# Board_v1.net
KiCad netlist of a schematic drawn in EAGLE
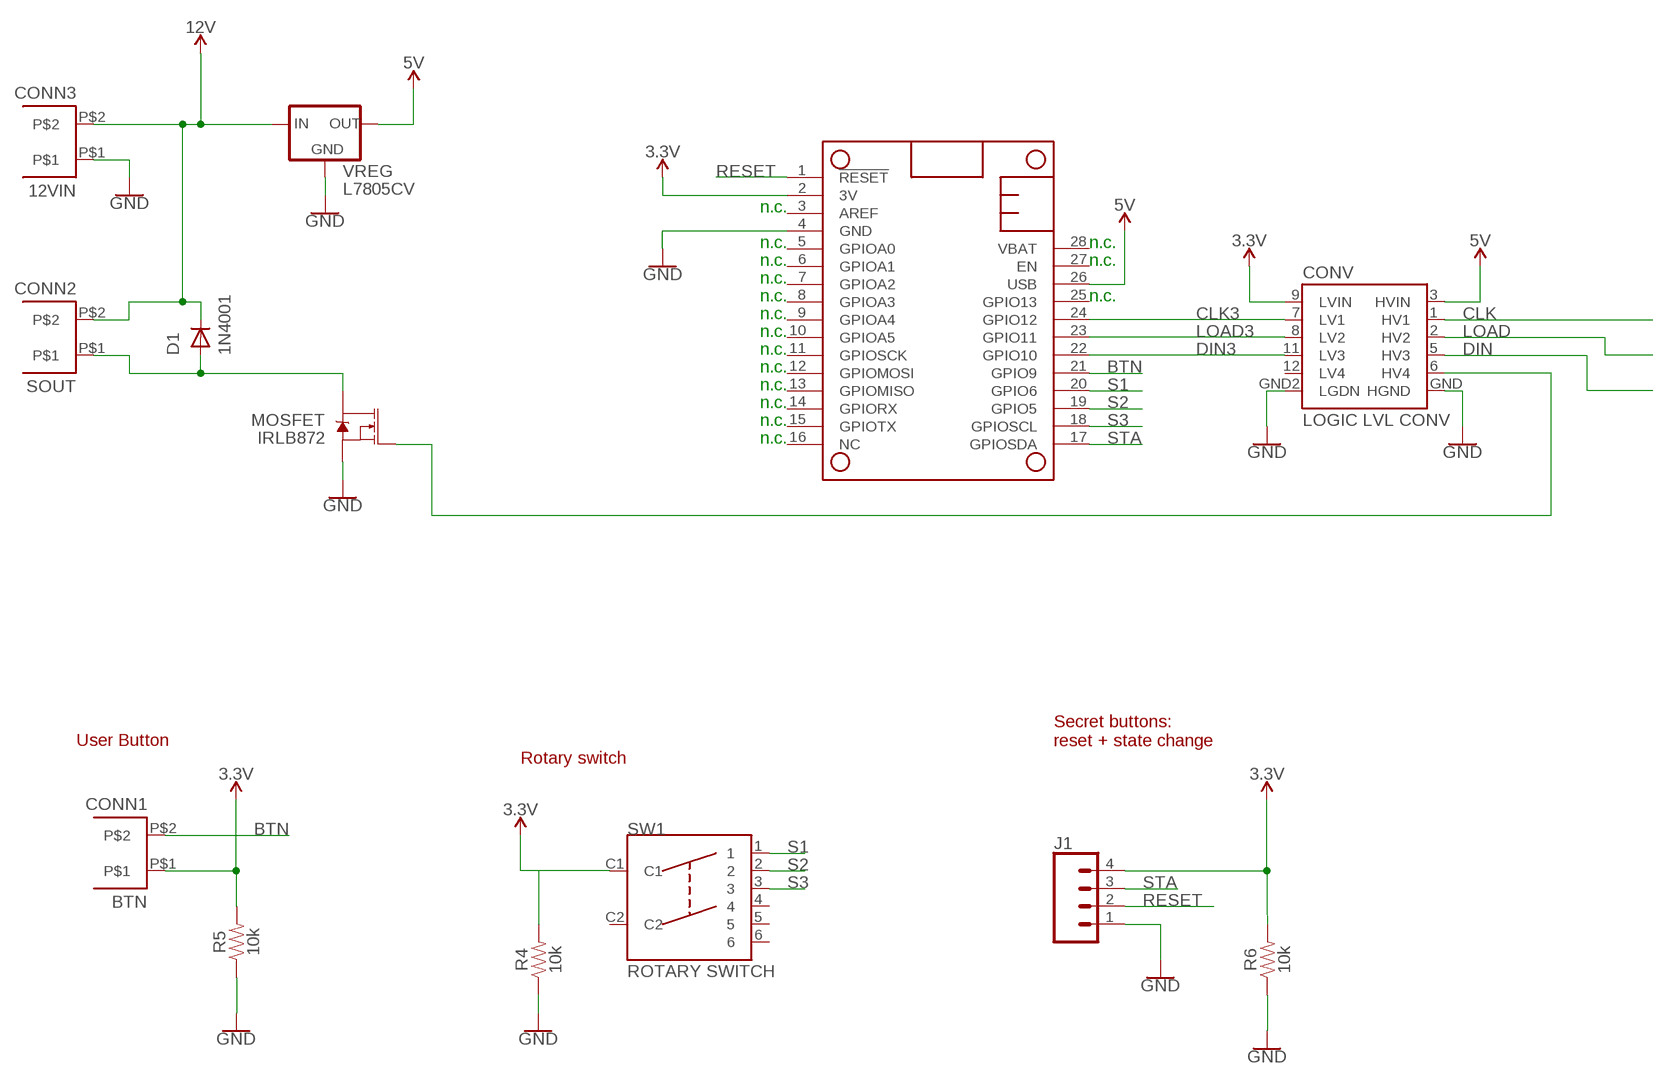
[diagram p0: schematic, sheet 1, part 1 of 3]
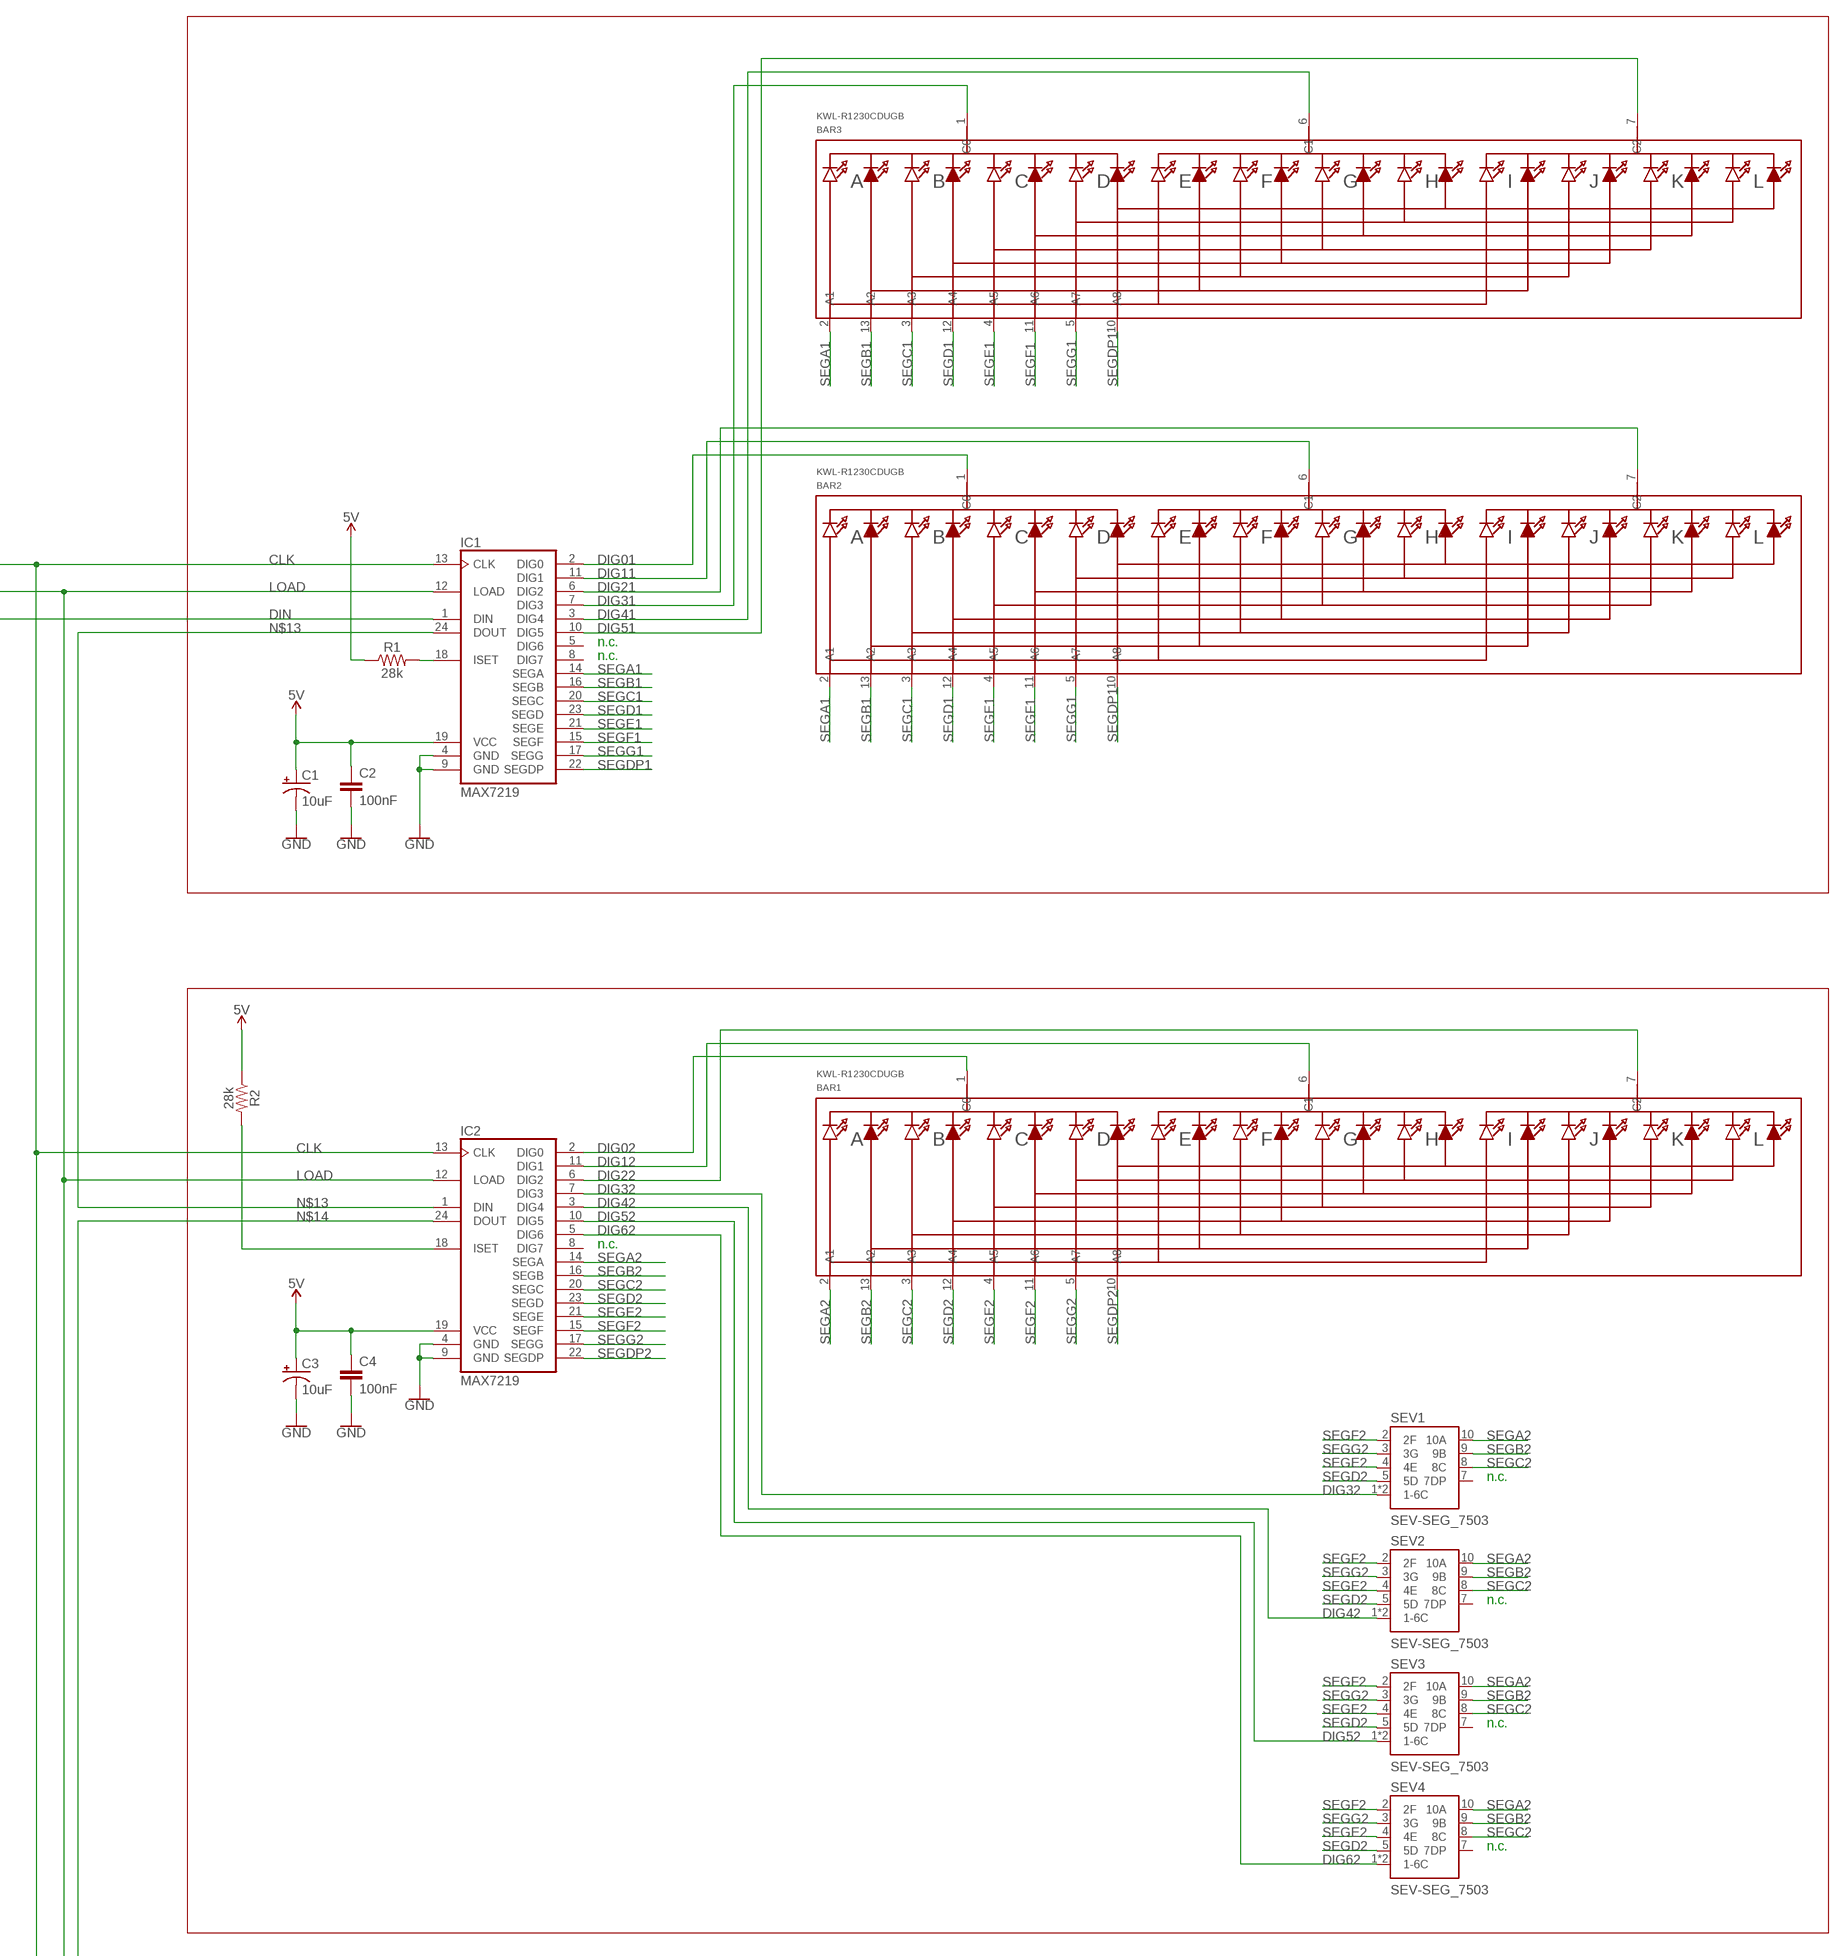
[diagram p1: schematic, sheet 1, part 2 of 3]
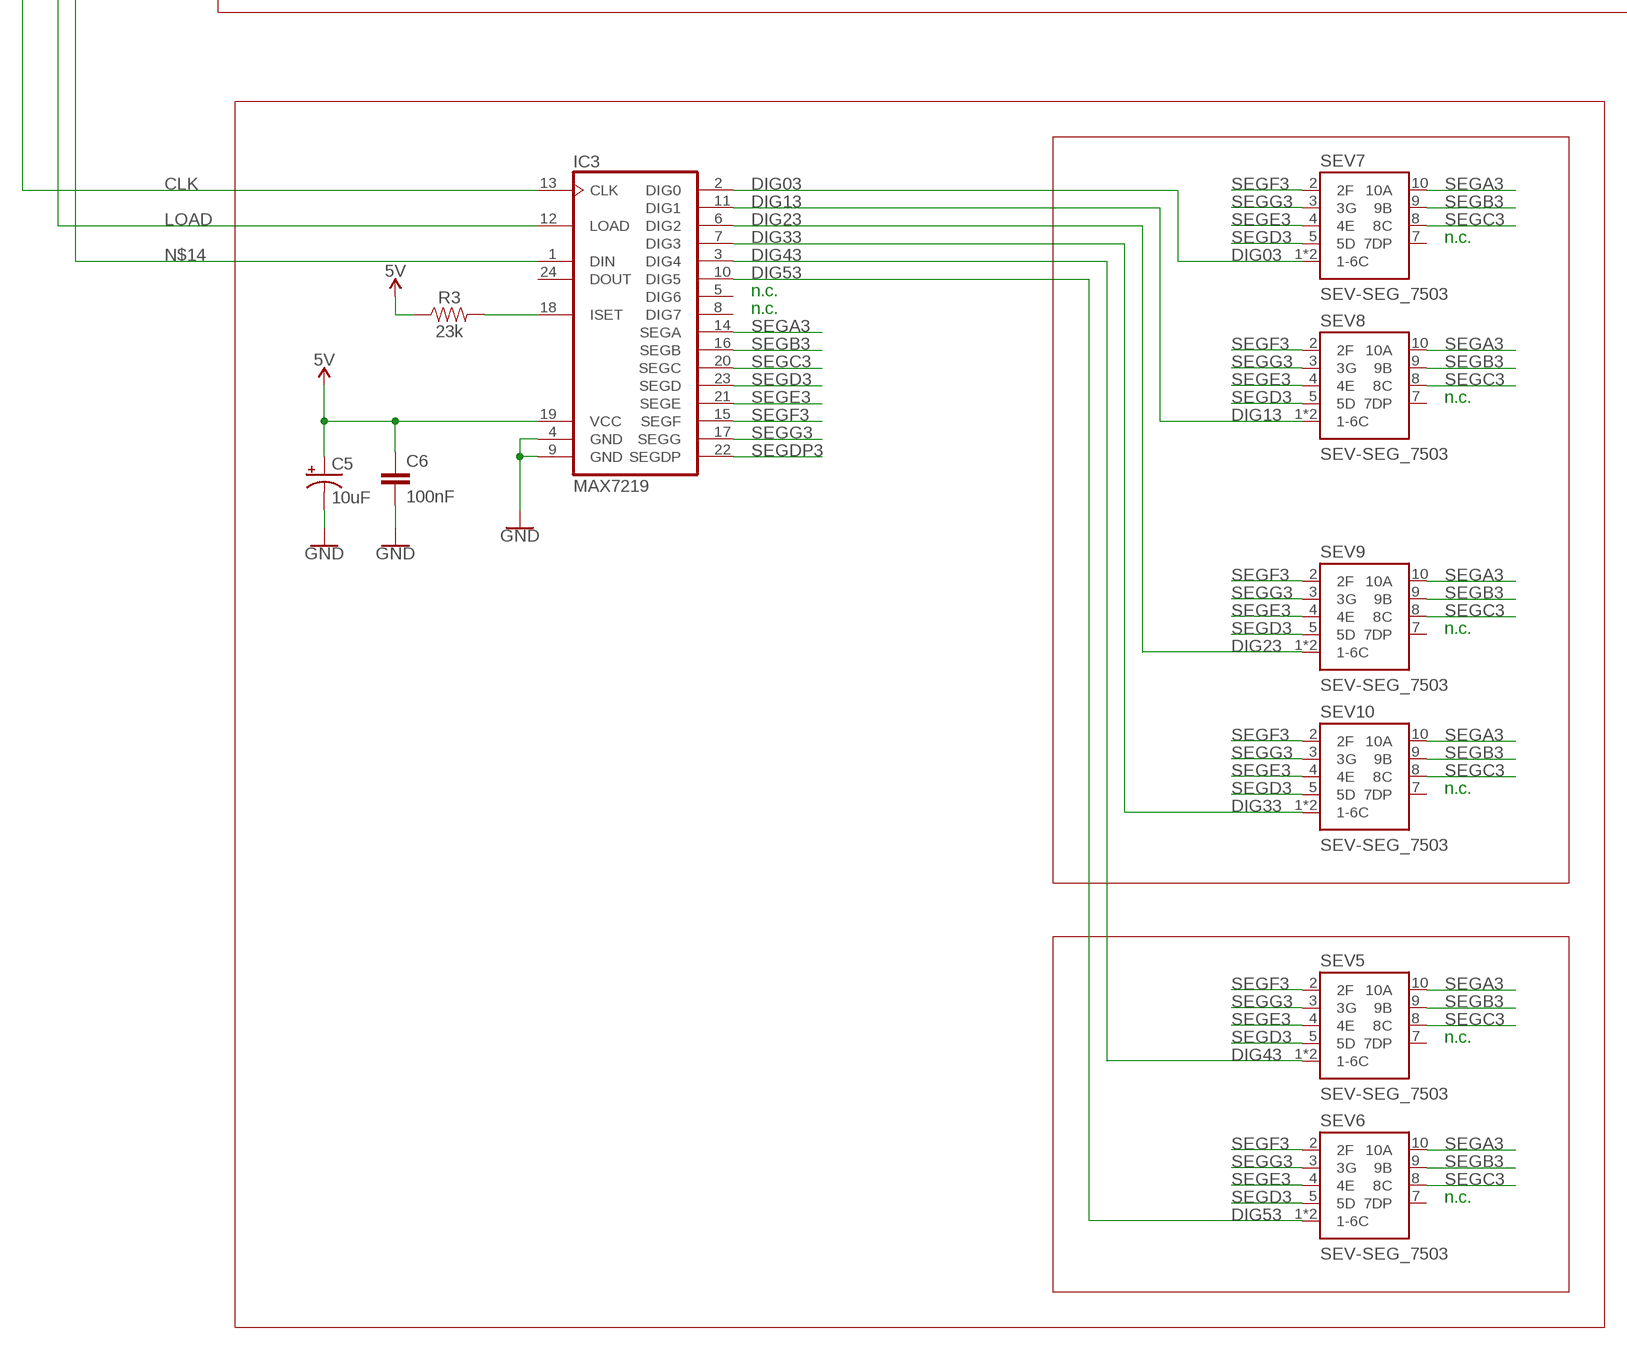
[diagram p2: schematic, sheet 1, part 3 of 3]

(export (version "E")
  (design (tool "Eeschema 10.0.6"))
  (components
    (comp (ref "12VIN")
      (value "CONN3")
      (footprint "eagle-import:MICRO-FIT_43560_3MM")
      (libsource (lib "eagle-import") (part "MICRO-FIT_3.0_43650"))
    )
    (comp (ref "BAR1")
      (value "KWL-R1230CDUGB")
      (footprint "eagle-import:SEGMENT_BICOL_BL-AR12Z3010")
      (libsource (lib "eagle-import") (part "KWL-R1230CDUGB"))
    )
    (comp (ref "BAR2")
      (value "KWL-R1230CDUGB")
      (footprint "eagle-import:SEGMENT_BICOL_BL-AR12Z3010")
      (libsource (lib "eagle-import") (part "KWL-R1230CDUGB"))
    )
    (comp (ref "BAR3")
      (value "KWL-R1230CDUGB")
      (footprint "eagle-import:SEGMENT_BICOL_BL-AR12Z3010")
      (libsource (lib "eagle-import") (part "KWL-R1230CDUGB"))
    )
    (comp (ref "BTN")
      (value "CONN1")
      (footprint "eagle-import:MICRO-FIT_43560_3MM")
      (libsource (lib "eagle-import") (part "MICRO-FIT_3.0_43650"))
    )
    (comp (ref "C1")
      (value "10uF")
      (footprint "eagle-import:CPOL-RADIAL-2.5MM-5MM-KIT")
      (libsource (lib "eagle-import") (part "CAP_POL"))
    )
    (comp (ref "C2")
      (value "100nF")
      (footprint "eagle-import:CAP-PTH-5MM")
      (libsource (lib "eagle-import") (part "CAP_CERAMIC"))
    )
    (comp (ref "C3")
      (value "10uF")
      (footprint "eagle-import:CPOL-RADIAL-2.5MM-5MM-KIT")
      (libsource (lib "eagle-import") (part "CAP_POL"))
    )
    (comp (ref "C4")
      (value "100nF")
      (footprint "eagle-import:CAP-PTH-5MM")
      (libsource (lib "eagle-import") (part "CAP_CERAMIC"))
    )
    (comp (ref "C5")
      (value "10uF")
      (footprint "eagle-import:CPOL-RADIAL-2.5MM-5MM-KIT")
      (libsource (lib "eagle-import") (part "CAP_POL"))
    )
    (comp (ref "C6")
      (value "100nF")
      (footprint "eagle-import:CAP-PTH-5MM")
      (libsource (lib "eagle-import") (part "CAP_CERAMIC"))
    )
    (comp (ref "CONV")
      (value "LOGIC LVL CONV")
      (footprint "eagle-import:3-5V_LOGIC_LVL_CONV")
      (libsource (lib "eagle-import") (part "3-5V_LOGIC_LVL_CONV"))
    )
    (comp (ref "D1")
      (value "1N4001")
      (footprint "eagle-import:CASE59−10-AXIAL")
      (libsource (lib "eagle-import") (part "1N4001"))
    )
    (comp (ref "FEATHERM0")
      (value "FEATHERWING_NODIM")
      (footprint "eagle-import:FEATHER")
      (libsource (lib "eagle-import") (part "FEATHERWING_NODIM"))
    )
    (comp (ref "IC1")
      (value "MAX7219")
      (footprint "eagle-import:DIL24-3")
      (fields (field (name "MF") "MAXIM") (field (name "MPN") "MAX7219CNG"))
      (libsource (lib "eagle-import") (part "MAX7219CNG"))
    )
    (comp (ref "IC2")
      (value "MAX7219")
      (footprint "eagle-import:DIL24-3")
      (fields (field (name "MF") "MAXIM") (field (name "MPN") "MAX7219CNG"))
      (libsource (lib "eagle-import") (part "MAX7219CNG"))
    )
    (comp (ref "IC3")
      (value "MAX7219")
      (footprint "eagle-import:DIL24-3")
      (fields (field (name "MF") "MAXIM") (field (name "MPN") "MAX7219CNG"))
      (libsource (lib "eagle-import") (part "MAX7219CNG"))
    )
    (comp (ref "J1")
      (value "CONN_041X04_NO_SILK")
      (footprint "eagle-import:1X04_NO_SILK")
      (libsource (lib "eagle-import") (part "CONN_041X04_NO_SILK"))
    )
    (comp (ref "MOSFET")
      (value "IRLB872")
      (footprint "eagle-import:TO-220-ALT")
      (libsource (lib "eagle-import") (part "IRLB872"))
    )
    (comp (ref "R1")
      (value "28k")
      (footprint "eagle-import:AXIAL-0.3")
      (libsource (lib "eagle-import") (part "RESISTOR"))
    )
    (comp (ref "R2")
      (value "28k")
      (footprint "eagle-import:AXIAL-0.3")
      (libsource (lib "eagle-import") (part "RESISTOR"))
    )
    (comp (ref "R3")
      (value "23k")
      (footprint "eagle-import:AXIAL-0.3")
      (libsource (lib "eagle-import") (part "RESISTOR"))
    )
    (comp (ref "R4")
      (value "10k")
      (footprint "eagle-import:AXIAL-0.3")
      (libsource (lib "eagle-import") (part "RESISTOR"))
    )
    (comp (ref "R5")
      (value "10k")
      (footprint "eagle-import:AXIAL-0.3")
      (libsource (lib "eagle-import") (part "RESISTOR"))
    )
    (comp (ref "R6")
      (value "10k")
      (footprint "eagle-import:AXIAL-0.3")
      (libsource (lib "eagle-import") (part "RESISTOR"))
    )
    (comp (ref "SEV1")
      (value "SEV-SEG_7503")
      (footprint "eagle-import:HDSP-7503-C")
      (libsource (lib "eagle-import") (part "SEV-SEG_7503"))
    )
    (comp (ref "SEV2")
      (value "SEV-SEG_7503")
      (footprint "eagle-import:HDSP-7503-C")
      (libsource (lib "eagle-import") (part "SEV-SEG_7503"))
    )
    (comp (ref "SEV3")
      (value "SEV-SEG_7503")
      (footprint "eagle-import:HDSP-7503-C")
      (libsource (lib "eagle-import") (part "SEV-SEG_7503"))
    )
    (comp (ref "SEV4")
      (value "SEV-SEG_7503")
      (footprint "eagle-import:HDSP-7503-C")
      (libsource (lib "eagle-import") (part "SEV-SEG_7503"))
    )
    (comp (ref "SEV5")
      (value "SEV-SEG_7503")
      (footprint "eagle-import:HDSP-7503-C")
      (libsource (lib "eagle-import") (part "SEV-SEG_7503"))
    )
    (comp (ref "SEV6")
      (value "SEV-SEG_7503")
      (footprint "eagle-import:HDSP-7503-C")
      (libsource (lib "eagle-import") (part "SEV-SEG_7503"))
    )
    (comp (ref "SEV7")
      (value "SEV-SEG_7503")
      (footprint "eagle-import:HDSP-7503-C")
      (libsource (lib "eagle-import") (part "SEV-SEG_7503"))
    )
    (comp (ref "SEV8")
      (value "SEV-SEG_7503")
      (footprint "eagle-import:HDSP-7503-C")
      (libsource (lib "eagle-import") (part "SEV-SEG_7503"))
    )
    (comp (ref "SEV9")
      (value "SEV-SEG_7503")
      (footprint "eagle-import:HDSP-7503-C")
      (libsource (lib "eagle-import") (part "SEV-SEG_7503"))
    )
    (comp (ref "SEV10")
      (value "SEV-SEG_7503")
      (footprint "eagle-import:HDSP-7503-C")
      (libsource (lib "eagle-import") (part "SEV-SEG_7503"))
    )
    (comp (ref "SOUT")
      (value "CONN2")
      (footprint "eagle-import:MICRO-FIT_43560_3MM")
      (libsource (lib "eagle-import") (part "MICRO-FIT_3.0_43650"))
    )
    (comp (ref "SW1")
      (value "ROTARY SWITCH")
      (footprint "eagle-import:MRB24B_SP3T")
      (libsource (lib "eagle-import") (part "MRB_ROTARY_SWITCH"))
    )
    (comp (ref "VREG")
      (value "L7805CV")
      (footprint "eagle-import:TO-220-ALT")
      (libsource (lib "eagle-import") (part "L7805CV"))
    )
  )
  (nets
    (net (code "1") (name "/BTN") (class "Default")
      (node (ref "BTN") (pin "P$2") (pinfunction "P$2_P$2") (pintype "bidirectional"))
      (node (ref "FEATHERM0") (pin "21") (pinfunction "GPIO9_21") (pintype "bidirectional"))
    )
    (net (code "2") (name "/CLK") (class "Default")
      (node (ref "CONV") (pin "1") (pinfunction "HV1_1") (pintype "bidirectional"))
      (node (ref "IC1") (pin "13") (pinfunction "CLK_13") (pintype "input"))
      (node (ref "IC2") (pin "13") (pinfunction "CLK_13") (pintype "input"))
      (node (ref "IC3") (pin "13") (pinfunction "CLK_13") (pintype "input"))
    )
    (net (code "3") (name "/CLK3") (class "Default")
      (node (ref "CONV") (pin "7") (pinfunction "LV1_7") (pintype "bidirectional"))
      (node (ref "FEATHERM0") (pin "24") (pinfunction "GPIO12_24") (pintype "bidirectional"))
    )
    (net (code "4") (name "/DIG01") (class "Default")
      (node (ref "BAR2") (pin "1") (pinfunction "C0_1") (pintype "bidirectional"))
      (node (ref "IC1") (pin "2") (pinfunction "DIG0_2") (pintype "output"))
    )
    (net (code "5") (name "/DIG02") (class "Default")
      (node (ref "BAR1") (pin "1") (pinfunction "C0_1") (pintype "bidirectional"))
      (node (ref "IC2") (pin "2") (pinfunction "DIG0_2") (pintype "output"))
    )
    (net (code "6") (name "/DIG03") (class "Default")
      (node (ref "IC3") (pin "2") (pinfunction "DIG0_2") (pintype "output"))
      (node (ref "SEV7") (pin "1") (pinfunction "1-6C_1") (pintype "bidirectional"))
      (node (ref "SEV7") (pin "6") (pinfunction "1-6C_6") (pintype "bidirectional"))
    )
    (net (code "7") (name "/DIG11") (class "Default")
      (node (ref "BAR2") (pin "6") (pinfunction "C1_6") (pintype "bidirectional"))
      (node (ref "IC1") (pin "11") (pinfunction "DIG1_11") (pintype "output"))
    )
    (net (code "8") (name "/DIG12") (class "Default")
      (node (ref "BAR1") (pin "6") (pinfunction "C1_6") (pintype "bidirectional"))
      (node (ref "IC2") (pin "11") (pinfunction "DIG1_11") (pintype "output"))
    )
    (net (code "9") (name "/DIG13") (class "Default")
      (node (ref "IC3") (pin "11") (pinfunction "DIG1_11") (pintype "output"))
      (node (ref "SEV8") (pin "1") (pinfunction "1-6C_1") (pintype "bidirectional"))
      (node (ref "SEV8") (pin "6") (pinfunction "1-6C_6") (pintype "bidirectional"))
    )
    (net (code "10") (name "/DIG21") (class "Default")
      (node (ref "BAR2") (pin "7") (pinfunction "C2_7") (pintype "bidirectional"))
      (node (ref "IC1") (pin "6") (pinfunction "DIG2_6") (pintype "output"))
    )
    (net (code "11") (name "/DIG22") (class "Default")
      (node (ref "BAR1") (pin "7") (pinfunction "C2_7") (pintype "bidirectional"))
      (node (ref "IC2") (pin "6") (pinfunction "DIG2_6") (pintype "output"))
    )
    (net (code "12") (name "/DIG23") (class "Default")
      (node (ref "IC3") (pin "6") (pinfunction "DIG2_6") (pintype "output"))
      (node (ref "SEV9") (pin "1") (pinfunction "1-6C_1") (pintype "bidirectional"))
      (node (ref "SEV9") (pin "6") (pinfunction "1-6C_6") (pintype "bidirectional"))
    )
    (net (code "13") (name "/DIG31") (class "Default")
      (node (ref "BAR3") (pin "1") (pinfunction "C0_1") (pintype "bidirectional"))
      (node (ref "IC1") (pin "7") (pinfunction "DIG3_7") (pintype "output"))
    )
    (net (code "14") (name "/DIG32") (class "Default")
      (node (ref "IC2") (pin "7") (pinfunction "DIG3_7") (pintype "output"))
      (node (ref "SEV1") (pin "1") (pinfunction "1-6C_1") (pintype "bidirectional"))
      (node (ref "SEV1") (pin "6") (pinfunction "1-6C_6") (pintype "bidirectional"))
    )
    (net (code "15") (name "/DIG33") (class "Default")
      (node (ref "IC3") (pin "7") (pinfunction "DIG3_7") (pintype "output"))
      (node (ref "SEV10") (pin "1") (pinfunction "1-6C_1") (pintype "bidirectional"))
      (node (ref "SEV10") (pin "6") (pinfunction "1-6C_6") (pintype "bidirectional"))
    )
    (net (code "16") (name "/DIG41") (class "Default")
      (node (ref "BAR3") (pin "6") (pinfunction "C1_6") (pintype "bidirectional"))
      (node (ref "IC1") (pin "3") (pinfunction "DIG4_3") (pintype "output"))
    )
    (net (code "17") (name "/DIG42") (class "Default")
      (node (ref "IC2") (pin "3") (pinfunction "DIG4_3") (pintype "output"))
      (node (ref "SEV2") (pin "1") (pinfunction "1-6C_1") (pintype "bidirectional"))
      (node (ref "SEV2") (pin "6") (pinfunction "1-6C_6") (pintype "bidirectional"))
    )
    (net (code "18") (name "/DIG43") (class "Default")
      (node (ref "IC3") (pin "3") (pinfunction "DIG4_3") (pintype "output"))
      (node (ref "SEV5") (pin "1") (pinfunction "1-6C_1") (pintype "bidirectional"))
      (node (ref "SEV5") (pin "6") (pinfunction "1-6C_6") (pintype "bidirectional"))
    )
    (net (code "19") (name "/DIG51") (class "Default")
      (node (ref "BAR3") (pin "7") (pinfunction "C2_7") (pintype "bidirectional"))
      (node (ref "IC1") (pin "10") (pinfunction "DIG5_10") (pintype "output"))
    )
    (net (code "20") (name "/DIG52") (class "Default")
      (node (ref "IC2") (pin "10") (pinfunction "DIG5_10") (pintype "output"))
      (node (ref "SEV3") (pin "1") (pinfunction "1-6C_1") (pintype "bidirectional"))
      (node (ref "SEV3") (pin "6") (pinfunction "1-6C_6") (pintype "bidirectional"))
    )
    (net (code "21") (name "/DIG53") (class "Default")
      (node (ref "IC3") (pin "10") (pinfunction "DIG5_10") (pintype "output"))
      (node (ref "SEV6") (pin "1") (pinfunction "1-6C_1") (pintype "bidirectional"))
      (node (ref "SEV6") (pin "6") (pinfunction "1-6C_6") (pintype "bidirectional"))
    )
    (net (code "22") (name "/DIG62") (class "Default")
      (node (ref "IC2") (pin "5") (pinfunction "DIG6_5") (pintype "output"))
      (node (ref "SEV4") (pin "1") (pinfunction "1-6C_1") (pintype "bidirectional"))
      (node (ref "SEV4") (pin "6") (pinfunction "1-6C_6") (pintype "bidirectional"))
    )
    (net (code "23") (name "/DIN") (class "Default")
      (node (ref "CONV") (pin "5") (pinfunction "HV3_5") (pintype "bidirectional"))
      (node (ref "IC1") (pin "1") (pinfunction "DIN_1") (pintype "input"))
    )
    (net (code "24") (name "/DIN3") (class "Default")
      (node (ref "CONV") (pin "11") (pinfunction "LV3_11") (pintype "bidirectional"))
      (node (ref "FEATHERM0") (pin "22") (pinfunction "GPIO10_22") (pintype "bidirectional"))
    )
    (net (code "25") (name "/LOAD") (class "Default")
      (node (ref "CONV") (pin "2") (pinfunction "HV2_2") (pintype "bidirectional"))
      (node (ref "IC1") (pin "12") (pinfunction "LOAD_12") (pintype "input"))
      (node (ref "IC2") (pin "12") (pinfunction "LOAD_12") (pintype "input"))
      (node (ref "IC3") (pin "12") (pinfunction "LOAD_12") (pintype "input"))
    )
    (net (code "26") (name "/LOAD3") (class "Default")
      (node (ref "CONV") (pin "8") (pinfunction "LV2_8") (pintype "bidirectional"))
      (node (ref "FEATHERM0") (pin "23") (pinfunction "GPIO11_23") (pintype "bidirectional"))
    )
    (net (code "27") (name "/N$13") (class "Default")
      (node (ref "IC1") (pin "24") (pinfunction "DOUT_24") (pintype "output"))
      (node (ref "IC2") (pin "1") (pinfunction "DIN_1") (pintype "input"))
    )
    (net (code "28") (name "/N$14") (class "Default")
      (node (ref "IC2") (pin "24") (pinfunction "DOUT_24") (pintype "output"))
      (node (ref "IC3") (pin "1") (pinfunction "DIN_1") (pintype "input"))
    )
    (net (code "29") (name "/RESET") (class "Default")
      (node (ref "FEATHERM0") (pin "1") (pinfunction "~{RESET}_1") (pintype "input"))
      (node (ref "J1") (pin "2") (pinfunction "2_2") (pintype "passive"))
    )
    (net (code "30") (name "/S1") (class "Default")
      (node (ref "FEATHERM0") (pin "20") (pinfunction "GPIO6_20") (pintype "bidirectional"))
      (node (ref "SW1") (pin "1") (pinfunction "1_1") (pintype "bidirectional"))
    )
    (net (code "31") (name "/S2") (class "Default")
      (node (ref "FEATHERM0") (pin "19") (pinfunction "GPIO5_19") (pintype "bidirectional"))
      (node (ref "SW1") (pin "2") (pinfunction "2_2") (pintype "bidirectional"))
    )
    (net (code "32") (name "/S3") (class "Default")
      (node (ref "FEATHERM0") (pin "18") (pinfunction "GPIOSCL_18") (pintype "bidirectional"))
      (node (ref "SW1") (pin "3") (pinfunction "3_3") (pintype "bidirectional"))
    )
    (net (code "33") (name "/SEGA1") (class "Default")
      (node (ref "BAR2") (pin "2") (pinfunction "A1_2") (pintype "bidirectional"))
      (node (ref "BAR3") (pin "2") (pinfunction "A1_2") (pintype "bidirectional"))
      (node (ref "IC1") (pin "14") (pinfunction "SEGA_14") (pintype "output"))
    )
    (net (code "34") (name "/SEGA2") (class "Default")
      (node (ref "BAR1") (pin "2") (pinfunction "A1_2") (pintype "bidirectional"))
      (node (ref "IC2") (pin "14") (pinfunction "SEGA_14") (pintype "output"))
      (node (ref "SEV1") (pin "10") (pinfunction "10A_10") (pintype "bidirectional"))
      (node (ref "SEV2") (pin "10") (pinfunction "10A_10") (pintype "bidirectional"))
      (node (ref "SEV3") (pin "10") (pinfunction "10A_10") (pintype "bidirectional"))
      (node (ref "SEV4") (pin "10") (pinfunction "10A_10") (pintype "bidirectional"))
    )
    (net (code "35") (name "/SEGA3") (class "Default")
      (node (ref "IC3") (pin "14") (pinfunction "SEGA_14") (pintype "output"))
      (node (ref "SEV10") (pin "10") (pinfunction "10A_10") (pintype "bidirectional"))
      (node (ref "SEV5") (pin "10") (pinfunction "10A_10") (pintype "bidirectional"))
      (node (ref "SEV6") (pin "10") (pinfunction "10A_10") (pintype "bidirectional"))
      (node (ref "SEV7") (pin "10") (pinfunction "10A_10") (pintype "bidirectional"))
      (node (ref "SEV8") (pin "10") (pinfunction "10A_10") (pintype "bidirectional"))
      (node (ref "SEV9") (pin "10") (pinfunction "10A_10") (pintype "bidirectional"))
    )
    (net (code "36") (name "/SEGB1") (class "Default")
      (node (ref "BAR2") (pin "13") (pinfunction "A2_13") (pintype "bidirectional"))
      (node (ref "BAR3") (pin "13") (pinfunction "A2_13") (pintype "bidirectional"))
      (node (ref "IC1") (pin "16") (pinfunction "SEGB_16") (pintype "output"))
    )
    (net (code "37") (name "/SEGB2") (class "Default")
      (node (ref "BAR1") (pin "13") (pinfunction "A2_13") (pintype "bidirectional"))
      (node (ref "IC2") (pin "16") (pinfunction "SEGB_16") (pintype "output"))
      (node (ref "SEV1") (pin "9") (pinfunction "9B_9") (pintype "bidirectional"))
      (node (ref "SEV2") (pin "9") (pinfunction "9B_9") (pintype "bidirectional"))
      (node (ref "SEV3") (pin "9") (pinfunction "9B_9") (pintype "bidirectional"))
      (node (ref "SEV4") (pin "9") (pinfunction "9B_9") (pintype "bidirectional"))
    )
    (net (code "38") (name "/SEGB3") (class "Default")
      (node (ref "IC3") (pin "16") (pinfunction "SEGB_16") (pintype "output"))
      (node (ref "SEV10") (pin "9") (pinfunction "9B_9") (pintype "bidirectional"))
      (node (ref "SEV5") (pin "9") (pinfunction "9B_9") (pintype "bidirectional"))
      (node (ref "SEV6") (pin "9") (pinfunction "9B_9") (pintype "bidirectional"))
      (node (ref "SEV7") (pin "9") (pinfunction "9B_9") (pintype "bidirectional"))
      (node (ref "SEV8") (pin "9") (pinfunction "9B_9") (pintype "bidirectional"))
      (node (ref "SEV9") (pin "9") (pinfunction "9B_9") (pintype "bidirectional"))
    )
    (net (code "39") (name "/SEGC1") (class "Default")
      (node (ref "BAR2") (pin "3") (pinfunction "A3_3") (pintype "bidirectional"))
      (node (ref "BAR3") (pin "3") (pinfunction "A3_3") (pintype "bidirectional"))
      (node (ref "IC1") (pin "20") (pinfunction "SEGC_20") (pintype "output"))
    )
    (net (code "40") (name "/SEGC2") (class "Default")
      (node (ref "BAR1") (pin "3") (pinfunction "A3_3") (pintype "bidirectional"))
      (node (ref "IC2") (pin "20") (pinfunction "SEGC_20") (pintype "output"))
      (node (ref "SEV1") (pin "8") (pinfunction "8C_8") (pintype "bidirectional"))
      (node (ref "SEV2") (pin "8") (pinfunction "8C_8") (pintype "bidirectional"))
      (node (ref "SEV3") (pin "8") (pinfunction "8C_8") (pintype "bidirectional"))
      (node (ref "SEV4") (pin "8") (pinfunction "8C_8") (pintype "bidirectional"))
    )
    (net (code "41") (name "/SEGC3") (class "Default")
      (node (ref "IC3") (pin "20") (pinfunction "SEGC_20") (pintype "output"))
      (node (ref "SEV10") (pin "8") (pinfunction "8C_8") (pintype "bidirectional"))
      (node (ref "SEV5") (pin "8") (pinfunction "8C_8") (pintype "bidirectional"))
      (node (ref "SEV6") (pin "8") (pinfunction "8C_8") (pintype "bidirectional"))
      (node (ref "SEV7") (pin "8") (pinfunction "8C_8") (pintype "bidirectional"))
      (node (ref "SEV8") (pin "8") (pinfunction "8C_8") (pintype "bidirectional"))
      (node (ref "SEV9") (pin "8") (pinfunction "8C_8") (pintype "bidirectional"))
    )
    (net (code "42") (name "/SEGD1") (class "Default")
      (node (ref "BAR2") (pin "12") (pinfunction "A4_12") (pintype "bidirectional"))
      (node (ref "BAR3") (pin "12") (pinfunction "A4_12") (pintype "bidirectional"))
      (node (ref "IC1") (pin "23") (pinfunction "SEGD_23") (pintype "output"))
    )
    (net (code "43") (name "/SEGD2") (class "Default")
      (node (ref "BAR1") (pin "12") (pinfunction "A4_12") (pintype "bidirectional"))
      (node (ref "IC2") (pin "23") (pinfunction "SEGD_23") (pintype "output"))
      (node (ref "SEV1") (pin "5") (pinfunction "5D_5") (pintype "bidirectional"))
      (node (ref "SEV2") (pin "5") (pinfunction "5D_5") (pintype "bidirectional"))
      (node (ref "SEV3") (pin "5") (pinfunction "5D_5") (pintype "bidirectional"))
      (node (ref "SEV4") (pin "5") (pinfunction "5D_5") (pintype "bidirectional"))
    )
    (net (code "44") (name "/SEGD3") (class "Default")
      (node (ref "IC3") (pin "23") (pinfunction "SEGD_23") (pintype "output"))
      (node (ref "SEV10") (pin "5") (pinfunction "5D_5") (pintype "bidirectional"))
      (node (ref "SEV5") (pin "5") (pinfunction "5D_5") (pintype "bidirectional"))
      (node (ref "SEV6") (pin "5") (pinfunction "5D_5") (pintype "bidirectional"))
      (node (ref "SEV7") (pin "5") (pinfunction "5D_5") (pintype "bidirectional"))
      (node (ref "SEV8") (pin "5") (pinfunction "5D_5") (pintype "bidirectional"))
      (node (ref "SEV9") (pin "5") (pinfunction "5D_5") (pintype "bidirectional"))
    )
    (net (code "45") (name "/SEGDP1") (class "Default")
      (node (ref "BAR2") (pin "10") (pinfunction "A8_10") (pintype "bidirectional"))
      (node (ref "BAR3") (pin "10") (pinfunction "A8_10") (pintype "bidirectional"))
      (node (ref "IC1") (pin "22") (pinfunction "SEGDP_22") (pintype "output"))
    )
    (net (code "46") (name "/SEGDP2") (class "Default")
      (node (ref "BAR1") (pin "10") (pinfunction "A8_10") (pintype "bidirectional"))
      (node (ref "IC2") (pin "22") (pinfunction "SEGDP_22") (pintype "output"))
    )
    (net (code "47") (name "/SEGDP3") (class "Default")
      (node (ref "IC3") (pin "22") (pinfunction "SEGDP_22") (pintype "output"))
      (node (ref "SEV6") (pin "7") (pinfunction "7DP_7") (pintype "bidirectional"))
      (node (ref "SEV7") (pin "7") (pinfunction "7DP_7") (pintype "bidirectional"))
      (node (ref "SEV9") (pin "7") (pinfunction "7DP_7") (pintype "bidirectional"))
    )
    (net (code "48") (name "/SEGE1") (class "Default")
      (node (ref "BAR2") (pin "4") (pinfunction "A5_4") (pintype "bidirectional"))
      (node (ref "BAR3") (pin "4") (pinfunction "A5_4") (pintype "bidirectional"))
      (node (ref "IC1") (pin "21") (pinfunction "SEGE_21") (pintype "output"))
    )
    (net (code "49") (name "/SEGE2") (class "Default")
      (node (ref "BAR1") (pin "4") (pinfunction "A5_4") (pintype "bidirectional"))
      (node (ref "IC2") (pin "21") (pinfunction "SEGE_21") (pintype "output"))
      (node (ref "SEV1") (pin "4") (pinfunction "4E_4") (pintype "bidirectional"))
      (node (ref "SEV2") (pin "4") (pinfunction "4E_4") (pintype "bidirectional"))
      (node (ref "SEV3") (pin "4") (pinfunction "4E_4") (pintype "bidirectional"))
      (node (ref "SEV4") (pin "4") (pinfunction "4E_4") (pintype "bidirectional"))
    )
    (net (code "50") (name "/SEGE3") (class "Default")
      (node (ref "IC3") (pin "21") (pinfunction "SEGE_21") (pintype "output"))
      (node (ref "SEV10") (pin "4") (pinfunction "4E_4") (pintype "bidirectional"))
      (node (ref "SEV5") (pin "4") (pinfunction "4E_4") (pintype "bidirectional"))
      (node (ref "SEV6") (pin "4") (pinfunction "4E_4") (pintype "bidirectional"))
      (node (ref "SEV7") (pin "4") (pinfunction "4E_4") (pintype "bidirectional"))
      (node (ref "SEV8") (pin "4") (pinfunction "4E_4") (pintype "bidirectional"))
      (node (ref "SEV9") (pin "4") (pinfunction "4E_4") (pintype "bidirectional"))
    )
    (net (code "51") (name "/SEGF1") (class "Default")
      (node (ref "BAR2") (pin "11") (pinfunction "A6_11") (pintype "bidirectional"))
      (node (ref "BAR3") (pin "11") (pinfunction "A6_11") (pintype "bidirectional"))
      (node (ref "IC1") (pin "15") (pinfunction "SEGF_15") (pintype "output"))
    )
    (net (code "52") (name "/SEGF2") (class "Default")
      (node (ref "BAR1") (pin "11") (pinfunction "A6_11") (pintype "bidirectional"))
      (node (ref "IC2") (pin "15") (pinfunction "SEGF_15") (pintype "output"))
      (node (ref "SEV1") (pin "2") (pinfunction "2F_2") (pintype "bidirectional"))
      (node (ref "SEV2") (pin "2") (pinfunction "2F_2") (pintype "bidirectional"))
      (node (ref "SEV3") (pin "2") (pinfunction "2F_2") (pintype "bidirectional"))
      (node (ref "SEV4") (pin "2") (pinfunction "2F_2") (pintype "bidirectional"))
    )
    (net (code "53") (name "/SEGF3") (class "Default")
      (node (ref "IC3") (pin "15") (pinfunction "SEGF_15") (pintype "output"))
      (node (ref "SEV10") (pin "2") (pinfunction "2F_2") (pintype "bidirectional"))
      (node (ref "SEV5") (pin "2") (pinfunction "2F_2") (pintype "bidirectional"))
      (node (ref "SEV6") (pin "2") (pinfunction "2F_2") (pintype "bidirectional"))
      (node (ref "SEV7") (pin "2") (pinfunction "2F_2") (pintype "bidirectional"))
      (node (ref "SEV8") (pin "2") (pinfunction "2F_2") (pintype "bidirectional"))
      (node (ref "SEV9") (pin "2") (pinfunction "2F_2") (pintype "bidirectional"))
    )
    (net (code "54") (name "/SEGG1") (class "Default")
      (node (ref "BAR2") (pin "5") (pinfunction "A7_5") (pintype "bidirectional"))
      (node (ref "BAR3") (pin "5") (pinfunction "A7_5") (pintype "bidirectional"))
      (node (ref "IC1") (pin "17") (pinfunction "SEGG_17") (pintype "output"))
    )
    (net (code "55") (name "/SEGG2") (class "Default")
      (node (ref "BAR1") (pin "5") (pinfunction "A7_5") (pintype "bidirectional"))
      (node (ref "IC2") (pin "17") (pinfunction "SEGG_17") (pintype "output"))
      (node (ref "SEV1") (pin "3") (pinfunction "3G_3") (pintype "bidirectional"))
      (node (ref "SEV2") (pin "3") (pinfunction "3G_3") (pintype "bidirectional"))
      (node (ref "SEV3") (pin "3") (pinfunction "3G_3") (pintype "bidirectional"))
      (node (ref "SEV4") (pin "3") (pinfunction "3G_3") (pintype "bidirectional"))
    )
    (net (code "56") (name "/SEGG3") (class "Default")
      (node (ref "IC3") (pin "17") (pinfunction "SEGG_17") (pintype "output"))
      (node (ref "SEV10") (pin "3") (pinfunction "3G_3") (pintype "bidirectional"))
      (node (ref "SEV5") (pin "3") (pinfunction "3G_3") (pintype "bidirectional"))
      (node (ref "SEV6") (pin "3") (pinfunction "3G_3") (pintype "bidirectional"))
      (node (ref "SEV7") (pin "3") (pinfunction "3G_3") (pintype "bidirectional"))
      (node (ref "SEV8") (pin "3") (pinfunction "3G_3") (pintype "bidirectional"))
      (node (ref "SEV9") (pin "3") (pinfunction "3G_3") (pintype "bidirectional"))
    )
    (net (code "57") (name "/STA") (class "Default")
      (node (ref "FEATHERM0") (pin "17") (pinfunction "GPIOSDA_17") (pintype "bidirectional"))
      (node (ref "J1") (pin "3") (pinfunction "3_3") (pintype "passive"))
    )
    (net (code "58") (name "/VBAT") (class "Default")
      (node (ref "FEATHERM0") (pin "28") (pinfunction "VBAT_28") (pintype "power_in"))
    )
    (net (code "59") (name "3.3V") (class "Default")
      (node (ref "BTN") (pin "P$1") (pinfunction "P$1_P$1") (pintype "bidirectional"))
      (node (ref "CONV") (pin "9") (pinfunction "LVIN_9") (pintype "bidirectional"))
      (node (ref "FEATHERM0") (pin "2") (pinfunction "3V_2") (pintype "power_in"))
      (node (ref "J1") (pin "4") (pinfunction "4_4") (pintype "passive"))
      (node (ref "R5") (pin "P$2") (pinfunction "2_P$2") (pintype "passive"))
      (node (ref "R6") (pin "P$2") (pinfunction "2_P$2") (pintype "passive"))
    )
    (net (code "60") (name "5V") (class "Default")
      (node (ref "C1") (pin "1") (pinfunction "+_1") (pintype "passive"))
      (node (ref "C2") (pin "1") (pinfunction "1_1") (pintype "passive"))
      (node (ref "C3") (pin "1") (pinfunction "+_1") (pintype "passive"))
      (node (ref "C4") (pin "1") (pinfunction "1_1") (pintype "passive"))
      (node (ref "C5") (pin "1") (pinfunction "+_1") (pintype "passive"))
      (node (ref "C6") (pin "1") (pinfunction "1_1") (pintype "passive"))
      (node (ref "CONV") (pin "3") (pinfunction "HVIN_3") (pintype "bidirectional"))
      (node (ref "FEATHERM0") (pin "26") (pinfunction "USB_26") (pintype "power_in"))
      (node (ref "IC1") (pin "19") (pinfunction "VCC_19") (pintype "power_in"))
      (node (ref "IC2") (pin "19") (pinfunction "VCC_19") (pintype "power_in"))
      (node (ref "IC3") (pin "19") (pinfunction "VCC_19") (pintype "power_in"))
      (node (ref "R1") (pin "P$1") (pinfunction "1_P$1") (pintype "passive"))
      (node (ref "R2") (pin "P$1") (pinfunction "1_P$1") (pintype "passive"))
      (node (ref "R3") (pin "P$1") (pinfunction "1_P$1") (pintype "passive"))
      (node (ref "VREG") (pin "OUT") (pinfunction "OUT_OUT") (pintype "passive"))
    )
    (net (code "61") (name "12V") (class "Default")
      (node (ref "12VIN") (pin "P$2") (pinfunction "P$2_P$2") (pintype "bidirectional"))
      (node (ref "D1") (pin "CAT") (pinfunction "C_CAT") (pintype "passive"))
      (node (ref "SOUT") (pin "P$2") (pinfunction "P$2_P$2") (pintype "bidirectional"))
      (node (ref "VREG") (pin "IN") (pinfunction "IN_IN") (pintype "input"))
    )
    (net (code "62") (name "GND") (class "Default")
      (node (ref "12VIN") (pin "P$1") (pinfunction "P$1_P$1") (pintype "bidirectional"))
      (node (ref "C1") (pin "2") (pinfunction "-_2") (pintype "passive"))
      (node (ref "C2") (pin "2") (pinfunction "2_2") (pintype "passive"))
      (node (ref "C3") (pin "2") (pinfunction "-_2") (pintype "passive"))
      (node (ref "C4") (pin "2") (pinfunction "2_2") (pintype "passive"))
      (node (ref "C5") (pin "2") (pinfunction "-_2") (pintype "passive"))
      (node (ref "C6") (pin "2") (pinfunction "2_2") (pintype "passive"))
      (node (ref "CONV") (pin "GND") (pinfunction "HGND_GND") (pintype "bidirectional"))
      (node (ref "CONV") (pin "GND2") (pinfunction "LGDN_GND2") (pintype "bidirectional"))
      (node (ref "FEATHERM0") (pin "4") (pinfunction "GND_4") (pintype "power_in"))
      (node (ref "IC1") (pin "4") (pinfunction "GND_4") (pintype "power_in"))
      (node (ref "IC1") (pin "9") (pinfunction "GND_9") (pintype "power_in"))
      (node (ref "IC2") (pin "4") (pinfunction "GND_4") (pintype "power_in"))
      (node (ref "IC2") (pin "9") (pinfunction "GND_9") (pintype "power_in"))
      (node (ref "IC3") (pin "4") (pinfunction "GND_4") (pintype "power_in"))
      (node (ref "IC3") (pin "9") (pinfunction "GND_9") (pintype "power_in"))
      (node (ref "J1") (pin "1") (pinfunction "1_1") (pintype "passive"))
      (node (ref "MOSFET") (pin "OUT") (pinfunction "S_OUT") (pintype "bidirectional"))
      (node (ref "R4") (pin "P$1") (pinfunction "1_P$1") (pintype "passive"))
      (node (ref "R5") (pin "P$1") (pinfunction "1_P$1") (pintype "passive"))
      (node (ref "R6") (pin "P$1") (pinfunction "1_P$1") (pintype "passive"))
      (node (ref "VREG") (pin "GND") (pinfunction "GND_GND") (pintype "input"))
    )
    (net (code "63") (name "Net-(CONV-HV4)") (class "Default")
      (node (ref "CONV") (pin "6") (pinfunction "HV4_6") (pintype "bidirectional"))
      (node (ref "MOSFET") (pin "IN") (pinfunction "G_IN") (pintype "bidirectional"))
    )
    (net (code "64") (name "Net-(D1-A)") (class "Default")
      (node (ref "D1") (pin "ANOD") (pinfunction "A_ANOD") (pintype "passive"))
      (node (ref "MOSFET") (pin "GND") (pinfunction "D_GND") (pintype "bidirectional"))
      (node (ref "SOUT") (pin "P$1") (pinfunction "P$1_P$1") (pintype "bidirectional"))
    )
    (net (code "65") (name "Net-(IC1-ISET)") (class "Default")
      (node (ref "IC1") (pin "18") (pinfunction "ISET_18") (pintype "input"))
      (node (ref "R1") (pin "P$2") (pinfunction "2_P$2") (pintype "passive"))
    )
    (net (code "66") (name "Net-(IC2-ISET)") (class "Default")
      (node (ref "IC2") (pin "18") (pinfunction "ISET_18") (pintype "input"))
      (node (ref "R2") (pin "P$2") (pinfunction "2_P$2") (pintype "passive"))
    )
    (net (code "67") (name "Net-(IC3-ISET)") (class "Default")
      (node (ref "IC3") (pin "18") (pinfunction "ISET_18") (pintype "input"))
      (node (ref "R3") (pin "P$2") (pinfunction "2_P$2") (pintype "passive"))
    )
    (net (code "68") (name "Net-(R4-2)") (class "Default")
      (node (ref "R4") (pin "P$2") (pinfunction "2_P$2") (pintype "passive"))
      (node (ref "SW1") (pin "C1") (pinfunction "C1_C1") (pintype "bidirectional"))
    )
    (net (code "69") (name "unconnected-(CONV-LV4-Pad12)") (class "Default")
      (node (ref "CONV") (pin "12") (pinfunction "LV4_12") (pintype "bidirectional"))
    )
    (net (code "70") (name "unconnected-(FEATHERM0-AREF-Pad3)") (class "Default")
      (node (ref "FEATHERM0") (pin "3") (pinfunction "AREF_3") (pintype "passive"))
    )
    (net (code "71") (name "unconnected-(FEATHERM0-EN-Pad27)") (class "Default")
      (node (ref "FEATHERM0") (pin "27") (pinfunction "EN_27") (pintype "passive"))
    )
    (net (code "72") (name "unconnected-(FEATHERM0-GPIO13-Pad25)") (class "Default")
      (node (ref "FEATHERM0") (pin "25") (pinfunction "GPIO13_25") (pintype "bidirectional"))
    )
    (net (code "73") (name "unconnected-(FEATHERM0-GPIOA0-Pad5)") (class "Default")
      (node (ref "FEATHERM0") (pin "5") (pinfunction "GPIOA0_5") (pintype "bidirectional"))
    )
    (net (code "74") (name "unconnected-(FEATHERM0-GPIOA1-Pad6)") (class "Default")
      (node (ref "FEATHERM0") (pin "6") (pinfunction "GPIOA1_6") (pintype "bidirectional"))
    )
    (net (code "75") (name "unconnected-(FEATHERM0-GPIOA2-Pad7)") (class "Default")
      (node (ref "FEATHERM0") (pin "7") (pinfunction "GPIOA2_7") (pintype "bidirectional"))
    )
    (net (code "76") (name "unconnected-(FEATHERM0-GPIOA3-Pad8)") (class "Default")
      (node (ref "FEATHERM0") (pin "8") (pinfunction "GPIOA3_8") (pintype "bidirectional"))
    )
    (net (code "77") (name "unconnected-(FEATHERM0-GPIOA4-Pad9)") (class "Default")
      (node (ref "FEATHERM0") (pin "9") (pinfunction "GPIOA4_9") (pintype "bidirectional"))
    )
    (net (code "78") (name "unconnected-(FEATHERM0-GPIOA5-Pad10)") (class "Default")
      (node (ref "FEATHERM0") (pin "10") (pinfunction "GPIOA5_10") (pintype "bidirectional"))
    )
    (net (code "79") (name "unconnected-(FEATHERM0-GPIOMISO-Pad13)") (class "Default")
      (node (ref "FEATHERM0") (pin "13") (pinfunction "GPIOMISO_13") (pintype "bidirectional"))
    )
    (net (code "80") (name "unconnected-(FEATHERM0-GPIOMOSI-Pad12)") (class "Default")
      (node (ref "FEATHERM0") (pin "12") (pinfunction "GPIOMOSI_12") (pintype "bidirectional"))
    )
    (net (code "81") (name "unconnected-(FEATHERM0-GPIORX-Pad14)") (class "Default")
      (node (ref "FEATHERM0") (pin "14") (pinfunction "GPIORX_14") (pintype "bidirectional"))
    )
    (net (code "82") (name "unconnected-(FEATHERM0-GPIOSCK-Pad11)") (class "Default")
      (node (ref "FEATHERM0") (pin "11") (pinfunction "GPIOSCK_11") (pintype "bidirectional"))
    )
    (net (code "83") (name "unconnected-(FEATHERM0-GPIOTX-Pad15)") (class "Default")
      (node (ref "FEATHERM0") (pin "15") (pinfunction "GPIOTX_15") (pintype "bidirectional"))
    )
    (net (code "84") (name "unconnected-(FEATHERM0-NC-Pad16)") (class "Default")
      (node (ref "FEATHERM0") (pin "16") (pinfunction "NC_16") (pintype "passive"))
    )
    (net (code "85") (name "unconnected-(IC1-DIG6-Pad5)") (class "Default")
      (node (ref "IC1") (pin "5") (pinfunction "DIG6_5") (pintype "output"))
    )
    (net (code "86") (name "unconnected-(IC1-DIG7-Pad8)") (class "Default")
      (node (ref "IC1") (pin "8") (pinfunction "DIG7_8") (pintype "output"))
    )
    (net (code "87") (name "unconnected-(IC2-DIG7-Pad8)") (class "Default")
      (node (ref "IC2") (pin "8") (pinfunction "DIG7_8") (pintype "output"))
    )
    (net (code "88") (name "unconnected-(IC3-DIG6-Pad5)") (class "Default")
      (node (ref "IC3") (pin "5") (pinfunction "DIG6_5") (pintype "output"))
    )
    (net (code "89") (name "unconnected-(IC3-DIG7-Pad8)") (class "Default")
      (node (ref "IC3") (pin "8") (pinfunction "DIG7_8") (pintype "output"))
    )
    (net (code "90") (name "unconnected-(IC3-DOUT-Pad24)") (class "Default")
      (node (ref "IC3") (pin "24") (pinfunction "DOUT_24") (pintype "output"))
    )
    (net (code "91") (name "unconnected-(SEV1-7DP-Pad7)") (class "Default")
      (node (ref "SEV1") (pin "7") (pinfunction "7DP_7") (pintype "bidirectional"))
    )
    (net (code "92") (name "unconnected-(SEV2-7DP-Pad7)") (class "Default")
      (node (ref "SEV2") (pin "7") (pinfunction "7DP_7") (pintype "bidirectional"))
    )
    (net (code "93") (name "unconnected-(SEV3-7DP-Pad7)") (class "Default")
      (node (ref "SEV3") (pin "7") (pinfunction "7DP_7") (pintype "bidirectional"))
    )
    (net (code "94") (name "unconnected-(SEV4-7DP-Pad7)") (class "Default")
      (node (ref "SEV4") (pin "7") (pinfunction "7DP_7") (pintype "bidirectional"))
    )
    (net (code "95") (name "unconnected-(SEV5-7DP-Pad7)") (class "Default")
      (node (ref "SEV5") (pin "7") (pinfunction "7DP_7") (pintype "bidirectional"))
    )
    (net (code "96") (name "unconnected-(SEV8-7DP-Pad7)") (class "Default")
      (node (ref "SEV8") (pin "7") (pinfunction "7DP_7") (pintype "bidirectional"))
    )
    (net (code "97") (name "unconnected-(SEV10-7DP-Pad7)") (class "Default")
      (node (ref "SEV10") (pin "7") (pinfunction "7DP_7") (pintype "bidirectional"))
    )
    (net (code "98") (name "unconnected-(SW1-Pad4)") (class "Default")
      (node (ref "SW1") (pin "4") (pinfunction "4_4") (pintype "bidirectional"))
    )
    (net (code "99") (name "unconnected-(SW1-Pad5)") (class "Default")
      (node (ref "SW1") (pin "5") (pinfunction "5_5") (pintype "bidirectional"))
    )
    (net (code "100") (name "unconnected-(SW1-Pad6)") (class "Default")
      (node (ref "SW1") (pin "6") (pinfunction "6_6") (pintype "bidirectional"))
    )
    (net (code "101") (name "unconnected-(SW1-PadC2)") (class "Default")
      (node (ref "SW1") (pin "C2") (pinfunction "C2_C2") (pintype "bidirectional"))
    )
  )
)
